# Peripherals.net
KiCad netlist of a schematic drawn in Altium Designer
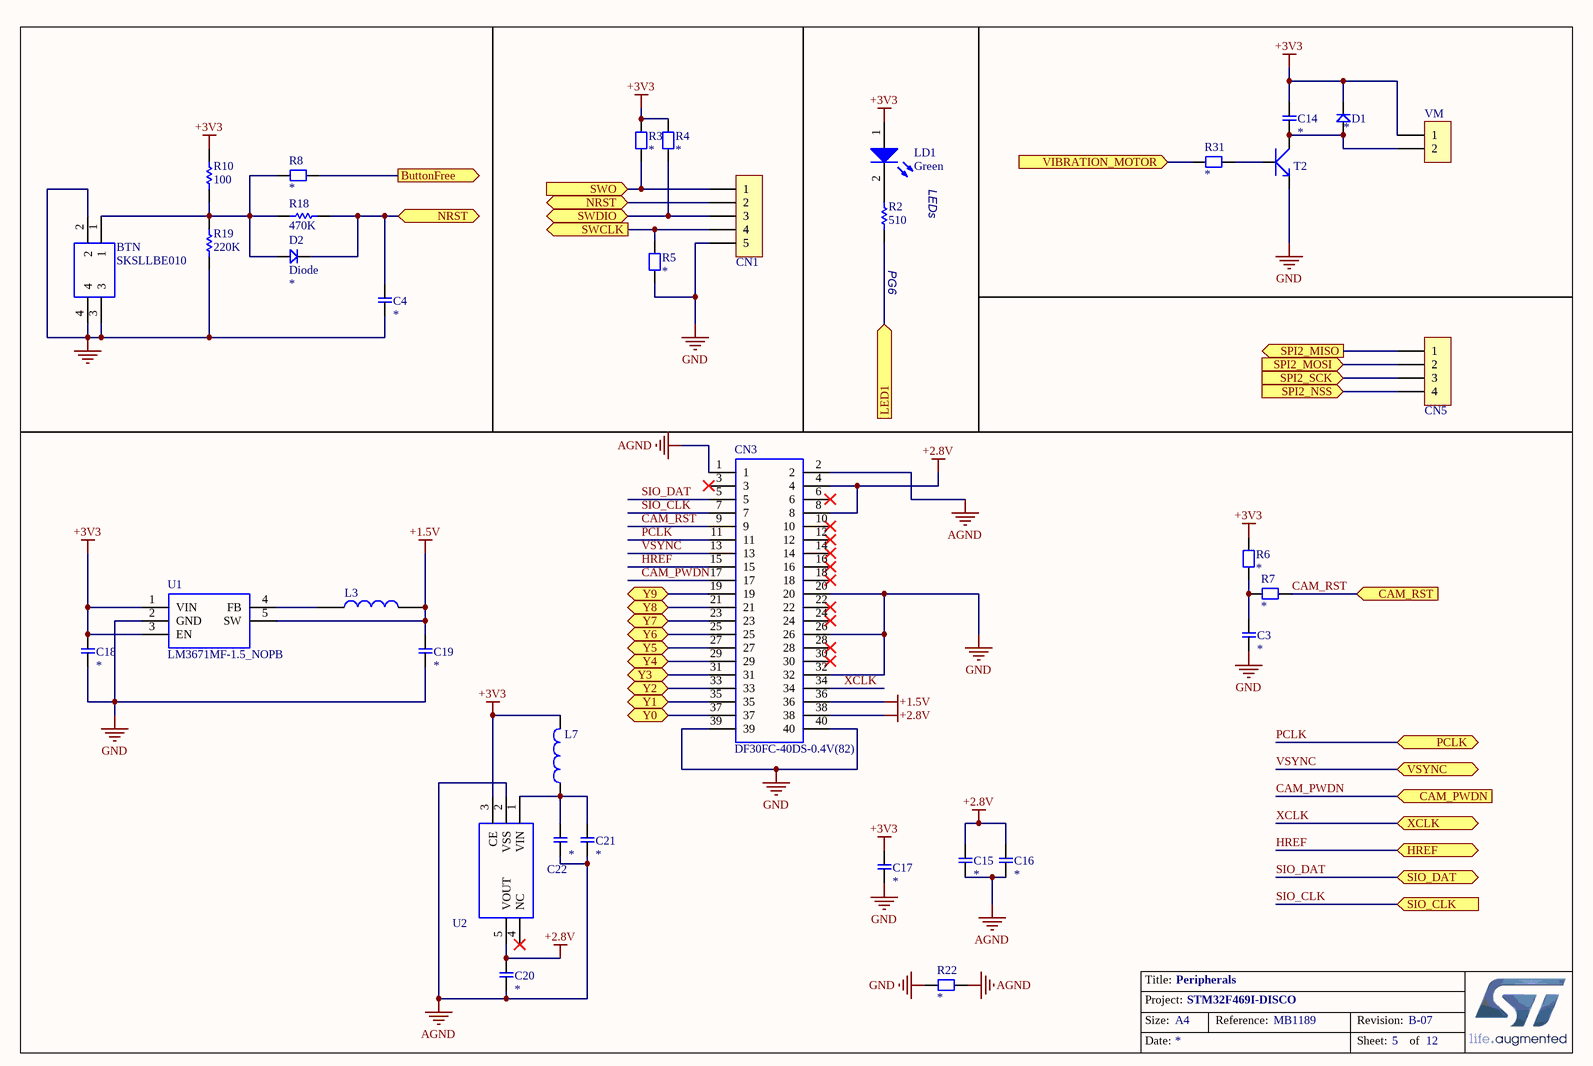
[diagram p0: Peripherals.SchDoc]

(export (version "E")
  (design (tool "Eeschema 10.0.6"))
  (components
    (comp (ref "BTN")
      (value "SKSLLBE010")
      (footprint "SKSLLBE010")
      (description "Black Button Tactile Switch, SPST-NO 50 mA 0.5mm Surface Mount")
      (fields (field (name "MOUSER PART NUMBER") "688-SKSLLBE010"))
      (libsource (lib "SKSLLBE010") (part "SKSLLBE010"))
    )
    (comp (ref "C3")
      (value "100 nF")
      (footprint "CAP - 0402")
      (fields (field (name "ALTIUM_VALUE") "*"))
      (libsource (lib "passives") (part "capacitor"))
    )
    (comp (ref "C4")
      (value "10uF")
      (footprint "CAP - 0805")
      (fields (field (name "ALTIUM_VALUE") "*"))
      (libsource (lib "passives") (part "capacitor"))
    )
    (comp (ref "C14")
      (value "100nF")
      (footprint "CAP - 0402")
      (fields (field (name "ALTIUM_VALUE") "*"))
      (libsource (lib "passives") (part "capacitor"))
    )
    (comp (ref "C15")
      (value "100nF")
      (footprint "CAP - 0402")
      (fields (field (name "ALTIUM_VALUE") "*"))
      (libsource (lib "passives") (part "capacitor"))
    )
    (comp (ref "C16")
      (value "100nF")
      (footprint "CAP - 0402")
      (fields (field (name "ALTIUM_VALUE") "*"))
      (libsource (lib "passives") (part "capacitor"))
    )
    (comp (ref "C17")
      (value "100nF")
      (footprint "CAP - 0402")
      (fields (field (name "ALTIUM_VALUE") "*"))
      (libsource (lib "passives") (part "capacitor"))
    )
    (comp (ref "C18")
      (value "4.7 uF")
      (footprint "CAP - 0603")
      (fields (field (name "ALTIUM_VALUE") "*"))
      (libsource (lib "passives") (part "capacitor"))
    )
    (comp (ref "C19")
      (value "10 uF")
      (footprint "CAP - 0402")
      (fields (field (name "ALTIUM_VALUE") "*"))
      (libsource (lib "passives") (part "capacitor"))
    )
    (comp (ref "C20")
      (value "1uF")
      (footprint "CAP - 0402")
      (fields (field (name "ALTIUM_VALUE") "*"))
      (libsource (lib "passives") (part "capacitor"))
    )
    (comp (ref "C21")
      (value "100nF")
      (footprint "CAP - 0402")
      (fields (field (name "ALTIUM_VALUE") "*"))
      (libsource (lib "passives") (part "capacitor"))
    )
    (comp (ref "C22")
      (value "10uF")
      (footprint "CAP - 0402")
      (fields (field (name "ALTIUM_VALUE") "*"))
      (libsource (lib "passives") (part "capacitor"))
    )
    (comp (ref "CN1")
      (value "Pin header 5p")
      (footprint "PIN HEADER 5P 2.54mm")
      (libsource (lib "connectors") (part "Pin header 5p"))
    )
    (comp (ref "CN3")
      (value "DF30FC-40DS-0.4V(82)")
      (footprint "DF30FC40DS04V82")
      (fields (field (name "RS PART NUMBER") "7008159"))
      (libsource (lib "DF30FC-40DS-0.4V(82)") (part "DF30FC-40DS-0.4V(82)"))
    )
    (comp (ref "CN5")
      (value "Pin header 4p")
      (footprint "Pin header 4p 1.27mm")
      (libsource (lib "connectors") (part "Pin header 4p"))
    )
    (comp (ref "D1")
      (value "Diode")
      (footprint "SOD123")
      (fields (field (name "TYPE") "*"))
      (libsource (lib "diode") (part "Diode"))
    )
    (comp (ref "D2")
      (value "Diode")
      (footprint "SOD123")
      (fields (field (name "TYPE") "*"))
      (libsource (lib "diode") (part "Diode"))
    )
    (comp (ref "L3")
      (value "2.2uH")
      (footprint "INDPM4532X280N")
      (description "587-3550-1-ND")
      (fields
        (field (name "MANUFACTURER_PART_NUMBER") "LQH43CN100K03L")
        (field (name "RS PART NUMBER") "7255165P")
      )
      (libsource (lib "LQH43CN100K03L") (part "LQH43CN100K03L"))
    )
    (comp (ref "L7")
      (value "BEAD(BK1608HS600-T)")
      (footprint "1608[0603]")
      (description "Inductor")
      (fields (field (name "PUBLISHER") "Altium Limited"))
      (libsource (lib "Miscellaneous Devices") (part "Inductor"))
    )
    (comp (ref "LD1")
      (value "Green")
      (footprint "LEDC1608X55N")
      (description "Typical RED, GREEN, YELLOW, AMBER GaAs LED")
      (fields (field (name "PUBLISHER") "Altium Limited"))
      (libsource (lib "Miscellaneous Devices") (part "LED2"))
    )
    (comp (ref "R2")
      (value "510")
      (footprint "RES - 0402")
      (description "Resistor")
      (fields (field (name "PUBLISHER") "Altium Limited"))
      (libsource (lib "Miscellaneous Devices") (part "Res1"))
    )
    (comp (ref "R3")
      (value "4K7")
      (footprint "RES - 0402")
      (fields (field (name "ALTIUM_VALUE") "*"))
      (libsource (lib "passives") (part "resistor"))
    )
    (comp (ref "R4")
      (value "4K7")
      (footprint "RES - 0402")
      (fields (field (name "ALTIUM_VALUE") "*"))
      (libsource (lib "passives") (part "resistor"))
    )
    (comp (ref "R5")
      (value "47K")
      (footprint "RES - 0402")
      (fields (field (name "ALTIUM_VALUE") "*"))
      (libsource (lib "passives") (part "resistor"))
    )
    (comp (ref "R6")
      (value "4K7")
      (footprint "RES - 0402")
      (fields (field (name "ALTIUM_VALUE") "*"))
      (libsource (lib "passives") (part "resistor"))
    )
    (comp (ref "R7")
      (value "0R")
      (footprint "RES - 0402")
      (fields (field (name "ALTIUM_VALUE") "*"))
      (libsource (lib "passives") (part "resistor"))
    )
    (comp (ref "R8")
      (value "10")
      (footprint "RES - 0402")
      (fields (field (name "ALTIUM_VALUE") "*"))
      (libsource (lib "passives") (part "resistor"))
    )
    (comp (ref "R10")
      (value "100")
      (footprint "RES - 0402")
      (description "Resistor")
      (fields (field (name "PUBLISHER") "Altium Limited"))
      (libsource (lib "Miscellaneous Devices") (part "Res1"))
    )
    (comp (ref "R18")
      (value "470K")
      (footprint "RES - 0603")
      (description "Resistor")
      (fields (field (name "PUBLISHER") "Altium Limited"))
      (libsource (lib "Miscellaneous Devices") (part "Res1"))
    )
    (comp (ref "R19")
      (value "220K")
      (footprint "RES - 0402")
      (description "Resistor")
      (fields (field (name "PUBLISHER") "Altium Limited"))
      (libsource (lib "Miscellaneous Devices") (part "res1"))
    )
    (comp (ref "R22")
      (value "0R")
      (footprint "RES - 0402")
      (fields (field (name "ALTIUM_VALUE") "*"))
      (libsource (lib "passives") (part "resistor"))
    )
    (comp (ref "R31")
      (value "1K")
      (footprint "RES - 0402")
      (fields (field (name "ALTIUM_VALUE") "*"))
      (libsource (lib "passives") (part "resistor"))
    )
    (comp (ref "T2") (value "BC817") (footprint "SOT23") (libsource (lib "transistors") (part "BC817")))
    (comp (ref "U1")
      (value "LM3671MF-1.5_NOPB")
      (footprint "SOT95P280X145-5N")
      (description "2MHz, 600mA Step-Down DC-DC Converter")
      (fields
        (field (name "MANUFACTURER_PART_NUMBER") "LM3671MF-1.5/NOPB")
        (field (name "RS PART NUMBER") "1624720")
      )
      (libsource (lib "LM3671MF-1.5_NOPB") (part "LM3671MF-1.5_NOPB"))
    )
    (comp (ref "U2")
      (value "AP7365-28WG-7DICT-ND")
      (footprint "SOT95P280X120-5N:SOT95P280X120-5N")
      (description "LDO Voltage Regulators 700mA High Speed Votage Regulator")
      (fields (field (name "MANUFACTURER_PART_NUMBER") "XC6210B302MR-G"))
      (libsource (lib "XC6210B302MR-G") (part "XC6210B302MR-G"))
    )
    (comp (ref "VM")
      (value "Pin header 2p")
      (footprint "RES - 0603")
      (libsource (lib "connectors") (part "Pin header 2p"))
    )
  )
  (nets
    (net (code "1") (name "+1.5V") (class "Default")
      (node (ref "C19") (pin "2") (pinfunction "2_2") (pintype "passive"))
      (node (ref "CN3") (pin "36") (pinfunction "36_36") (pintype "passive"))
      (node (ref "L3") (pin "2") (pinfunction "2_2") (pintype "passive"))
      (node (ref "U1") (pin "5") (pinfunction "SW_5") (pintype "passive"))
    )
    (net (code "2") (name "+2.8V") (class "Default")
      (node (ref "C15") (pin "1") (pinfunction "1_1") (pintype "passive"))
      (node (ref "C16") (pin "1") (pinfunction "1_1") (pintype "passive"))
      (node (ref "C20") (pin "1") (pinfunction "1_1") (pintype "passive"))
      (node (ref "CN3") (pin "38") (pinfunction "38_38") (pintype "passive"))
      (node (ref "CN3") (pin "4") (pinfunction "4_4") (pintype "passive"))
      (node (ref "CN3") (pin "8") (pinfunction "8_8") (pintype "passive"))
      (node (ref "U2") (pin "5") (pinfunction "VOUT_5") (pintype "passive"))
    )
    (net (code "3") (name "+3V3") (class "Default")
      (node (ref "C14") (pin "2") (pinfunction "2_2") (pintype "passive"))
      (node (ref "C17") (pin "1") (pinfunction "1_1") (pintype "passive"))
      (node (ref "C18") (pin "2") (pinfunction "2_2") (pintype "passive"))
      (node (ref "D1") (pin "2") (pinfunction "2_2") (pintype "passive"))
      (node (ref "L7") (pin "2") (pinfunction "2_2") (pintype "passive"))
      (node (ref "LD1") (pin "1") (pinfunction "A_1") (pintype "passive"))
      (node (ref "R10") (pin "2") (pinfunction "2_2") (pintype "passive"))
      (node (ref "R3") (pin "2") (pinfunction "2_2") (pintype "passive"))
      (node (ref "R4") (pin "2") (pinfunction "2_2") (pintype "passive"))
      (node (ref "R6") (pin "2") (pinfunction "2_2") (pintype "passive"))
      (node (ref "U1") (pin "1") (pinfunction "VIN_1") (pintype "passive"))
      (node (ref "U1") (pin "3") (pinfunction "EN_3") (pintype "passive"))
      (node (ref "U2") (pin "3") (pinfunction "CE_3") (pintype "passive"))
      (node (ref "VM") (pin "1") (pinfunction "1_1") (pintype "passive"))
    )
    (net (code "4") (name "/ButtonFree") (class "Default")
      (node (ref "R8") (pin "2") (pinfunction "2_2") (pintype "passive"))
    )
    (net (code "5") (name "/CAM_PWDN") (class "Default")
      (node (ref "CN3") (pin "17") (pinfunction "17_17") (pintype "passive"))
    )
    (net (code "6") (name "/CAM_RST") (class "Default")
      (node (ref "CN3") (pin "9") (pinfunction "9_9") (pintype "passive"))
      (node (ref "R7") (pin "1") (pinfunction "1_1") (pintype "passive"))
    )
    (net (code "7") (name "/HREF") (class "Default")
      (node (ref "CN3") (pin "15") (pinfunction "15_15") (pintype "passive"))
    )
    (net (code "8") (name "/LED1") (class "Default")
      (node (ref "R2") (pin "1") (pinfunction "1_1") (pintype "passive"))
    )
    (net (code "9") (name "/NRST") (class "Default")
      (node (ref "C4") (pin "2") (pinfunction "2_2") (pintype "passive"))
      (node (ref "CN1") (pin "2") (pinfunction "2_2") (pintype "passive"))
      (node (ref "D2") (pin "2") (pinfunction "2_2") (pintype "passive"))
      (node (ref "R18") (pin "2") (pinfunction "2_2") (pintype "passive"))
    )
    (net (code "10") (name "/PCLK") (class "Default")
      (node (ref "CN3") (pin "11") (pinfunction "11_11") (pintype "passive"))
    )
    (net (code "11") (name "/SIO_CLK") (class "Default")
      (node (ref "CN3") (pin "7") (pinfunction "7_7") (pintype "passive"))
    )
    (net (code "12") (name "/SIO_DAT") (class "Default")
      (node (ref "CN3") (pin "5") (pinfunction "5_5") (pintype "passive"))
    )
    (net (code "13") (name "/SPI2_MISO") (class "Default")
      (node (ref "CN5") (pin "1") (pinfunction "1_1") (pintype "passive"))
    )
    (net (code "14") (name "/SPI2_MOSI") (class "Default")
      (node (ref "CN5") (pin "2") (pinfunction "2_2") (pintype "passive"))
    )
    (net (code "15") (name "/SPI2_NSS") (class "Default")
      (node (ref "CN5") (pin "4") (pinfunction "4_4") (pintype "passive"))
    )
    (net (code "16") (name "/SPI2_SCK") (class "Default")
      (node (ref "CN5") (pin "3") (pinfunction "3_3") (pintype "passive"))
    )
    (net (code "17") (name "/SWCLK") (class "Default")
      (node (ref "CN1") (pin "4") (pinfunction "4_4") (pintype "passive"))
      (node (ref "R5") (pin "2") (pinfunction "2_2") (pintype "passive"))
    )
    (net (code "18") (name "/SWDIO") (class "Default")
      (node (ref "CN1") (pin "3") (pinfunction "3_3") (pintype "passive"))
      (node (ref "R4") (pin "1") (pinfunction "1_1") (pintype "passive"))
    )
    (net (code "19") (name "/SWO") (class "Default")
      (node (ref "CN1") (pin "1") (pinfunction "1_1") (pintype "passive"))
      (node (ref "R3") (pin "1") (pinfunction "1_1") (pintype "passive"))
    )
    (net (code "20") (name "/VIBRATION_MOTOR") (class "Default")
      (node (ref "R31") (pin "2") (pinfunction "2_2") (pintype "passive"))
    )
    (net (code "21") (name "/VSYNC") (class "Default")
      (node (ref "CN3") (pin "13") (pinfunction "13_13") (pintype "passive"))
    )
    (net (code "22") (name "/XCLK") (class "Default")
      (node (ref "CN3") (pin "34") (pinfunction "34_34") (pintype "passive"))
    )
    (net (code "23") (name "/Y0") (class "Default")
      (node (ref "CN3") (pin "37") (pinfunction "37_37") (pintype "passive"))
    )
    (net (code "24") (name "/Y1") (class "Default")
      (node (ref "CN3") (pin "35") (pinfunction "35_35") (pintype "passive"))
    )
    (net (code "25") (name "/Y2") (class "Default")
      (node (ref "CN3") (pin "33") (pinfunction "33_33") (pintype "passive"))
    )
    (net (code "26") (name "/Y3") (class "Default")
      (node (ref "CN3") (pin "31") (pinfunction "31_31") (pintype "passive"))
    )
    (net (code "27") (name "/Y4") (class "Default")
      (node (ref "CN3") (pin "29") (pinfunction "29_29") (pintype "passive"))
    )
    (net (code "28") (name "/Y5") (class "Default")
      (node (ref "CN3") (pin "27") (pinfunction "27_27") (pintype "passive"))
    )
    (net (code "29") (name "/Y6") (class "Default")
      (node (ref "CN3") (pin "25") (pinfunction "25_25") (pintype "passive"))
    )
    (net (code "30") (name "/Y7") (class "Default")
      (node (ref "CN3") (pin "23") (pinfunction "23_23") (pintype "passive"))
    )
    (net (code "31") (name "/Y8") (class "Default")
      (node (ref "CN3") (pin "21") (pinfunction "21_21") (pintype "passive"))
    )
    (net (code "32") (name "/Y9") (class "Default")
      (node (ref "CN3") (pin "19") (pinfunction "19_19") (pintype "passive"))
    )
    (net (code "33") (name "AGND") (class "Default")
      (node (ref "C15") (pin "2") (pinfunction "2_2") (pintype "passive"))
      (node (ref "C16") (pin "2") (pinfunction "2_2") (pintype "passive"))
      (node (ref "C20") (pin "2") (pinfunction "2_2") (pintype "passive"))
      (node (ref "C21") (pin "2") (pinfunction "2_2") (pintype "passive"))
      (node (ref "C22") (pin "2") (pinfunction "2_2") (pintype "passive"))
      (node (ref "CN3") (pin "1") (pinfunction "1_1") (pintype "passive"))
      (node (ref "CN3") (pin "2") (pinfunction "2_2") (pintype "passive"))
      (node (ref "R22") (pin "1") (pinfunction "1_1") (pintype "passive"))
      (node (ref "U2") (pin "2") (pinfunction "VSS_2") (pintype "passive"))
    )
    (net (code "34") (name "GND") (class "Default")
      (node (ref "BTN") (pin "2") (pinfunction "2_2") (pintype "passive"))
      (node (ref "BTN") (pin "3") (pinfunction "3_3") (pintype "passive"))
      (node (ref "BTN") (pin "4") (pinfunction "4_4") (pintype "passive"))
      (node (ref "C17") (pin "2") (pinfunction "2_2") (pintype "passive"))
      (node (ref "C18") (pin "1") (pinfunction "1_1") (pintype "passive"))
      (node (ref "C19") (pin "1") (pinfunction "1_1") (pintype "passive"))
      (node (ref "C3") (pin "2") (pinfunction "2_2") (pintype "passive"))
      (node (ref "C4") (pin "1") (pinfunction "1_1") (pintype "passive"))
      (node (ref "CN1") (pin "5") (pinfunction "5_5") (pintype "passive"))
      (node (ref "CN3") (pin "20") (pinfunction "20_20") (pintype "passive"))
      (node (ref "CN3") (pin "26") (pinfunction "26_26") (pintype "passive"))
      (node (ref "CN3") (pin "32") (pinfunction "32_32") (pintype "passive"))
      (node (ref "CN3") (pin "39") (pinfunction "39_39") (pintype "passive"))
      (node (ref "CN3") (pin "40") (pinfunction "40_40") (pintype "passive"))
      (node (ref "R19") (pin "2") (pinfunction "2_2") (pintype "passive"))
      (node (ref "R22") (pin "2") (pinfunction "2_2") (pintype "passive"))
      (node (ref "R5") (pin "1") (pinfunction "1_1") (pintype "passive"))
      (node (ref "T2") (pin "2") (pinfunction "2_2") (pintype "passive"))
      (node (ref "U1") (pin "2") (pinfunction "GND_2") (pintype "passive"))
    )
    (net (code "35") (name "Net-(BTN-Pad1)") (class "Default")
      (node (ref "BTN") (pin "1") (pinfunction "1_1") (pintype "passive"))
      (node (ref "D2") (pin "1") (pinfunction "1_1") (pintype "passive"))
      (node (ref "R10") (pin "1") (pinfunction "1_1") (pintype "passive"))
      (node (ref "R18") (pin "1") (pinfunction "1_1") (pintype "passive"))
      (node (ref "R19") (pin "1") (pinfunction "1_1") (pintype "passive"))
      (node (ref "R8") (pin "1") (pinfunction "1_1") (pintype "passive"))
    )
    (net (code "36") (name "Net-(C3-Pad1)") (class "Default")
      (node (ref "C3") (pin "1") (pinfunction "1_1") (pintype "passive"))
      (node (ref "R6") (pin "1") (pinfunction "1_1") (pintype "passive"))
      (node (ref "R7") (pin "2") (pinfunction "2_2") (pintype "passive"))
    )
    (net (code "37") (name "Net-(C14-Pad1)") (class "Default")
      (node (ref "C14") (pin "1") (pinfunction "1_1") (pintype "passive"))
      (node (ref "D1") (pin "1") (pinfunction "1_1") (pintype "passive"))
      (node (ref "T2") (pin "3") (pinfunction "3_3") (pintype "passive"))
      (node (ref "VM") (pin "2") (pinfunction "2_2") (pintype "passive"))
    )
    (net (code "38") (name "Net-(LD1-K)") (class "Default")
      (node (ref "LD1") (pin "2") (pinfunction "K_2") (pintype "passive"))
      (node (ref "R2") (pin "2") (pinfunction "2_2") (pintype "passive"))
    )
    (net (code "39") (name "Net-(R31-Pad1)") (class "Default")
      (node (ref "R31") (pin "1") (pinfunction "1_1") (pintype "passive"))
      (node (ref "T2") (pin "1") (pinfunction "1_1") (pintype "passive"))
    )
    (net (code "40") (name "Net-(U1-FB)") (class "Default")
      (node (ref "L3") (pin "1") (pinfunction "1_1") (pintype "passive"))
      (node (ref "U1") (pin "4") (pinfunction "FB_4") (pintype "passive"))
    )
    (net (code "41") (name "Net-(U2-VIN)") (class "Default")
      (node (ref "C21") (pin "1") (pinfunction "1_1") (pintype "passive"))
      (node (ref "C22") (pin "1") (pinfunction "1_1") (pintype "passive"))
      (node (ref "L7") (pin "1") (pinfunction "1_1") (pintype "passive"))
      (node (ref "U2") (pin "1") (pinfunction "VIN_1") (pintype "passive"))
    )
    (net (code "42") (name "unconnected-(CN3-Pad3)") (class "Default")
      (node (ref "CN3") (pin "3") (pinfunction "3_3") (pintype "passive+no_connect"))
    )
    (net (code "43") (name "unconnected-(CN3-Pad6)") (class "Default")
      (node (ref "CN3") (pin "6") (pinfunction "6_6") (pintype "passive+no_connect"))
    )
    (net (code "44") (name "unconnected-(CN3-Pad10)") (class "Default")
      (node (ref "CN3") (pin "10") (pinfunction "10_10") (pintype "passive+no_connect"))
    )
    (net (code "45") (name "unconnected-(CN3-Pad12)") (class "Default")
      (node (ref "CN3") (pin "12") (pinfunction "12_12") (pintype "passive+no_connect"))
    )
    (net (code "46") (name "unconnected-(CN3-Pad14)") (class "Default")
      (node (ref "CN3") (pin "14") (pinfunction "14_14") (pintype "passive+no_connect"))
    )
    (net (code "47") (name "unconnected-(CN3-Pad16)") (class "Default")
      (node (ref "CN3") (pin "16") (pinfunction "16_16") (pintype "passive+no_connect"))
    )
    (net (code "48") (name "unconnected-(CN3-Pad18)") (class "Default")
      (node (ref "CN3") (pin "18") (pinfunction "18_18") (pintype "passive+no_connect"))
    )
    (net (code "49") (name "unconnected-(CN3-Pad22)") (class "Default")
      (node (ref "CN3") (pin "22") (pinfunction "22_22") (pintype "passive+no_connect"))
    )
    (net (code "50") (name "unconnected-(CN3-Pad24)") (class "Default")
      (node (ref "CN3") (pin "24") (pinfunction "24_24") (pintype "passive+no_connect"))
    )
    (net (code "51") (name "unconnected-(CN3-Pad28)") (class "Default")
      (node (ref "CN3") (pin "28") (pinfunction "28_28") (pintype "passive+no_connect"))
    )
    (net (code "52") (name "unconnected-(CN3-Pad30)") (class "Default")
      (node (ref "CN3") (pin "30") (pinfunction "30_30") (pintype "passive+no_connect"))
    )
    (net (code "53") (name "unconnected-(U2-NC-Pad4)") (class "Default")
      (node (ref "U2") (pin "4") (pinfunction "NC_4") (pintype "passive+no_connect"))
    )
  )
)
